# ASPLY.net
KiCad netlist of a schematic drawn in EAGLE
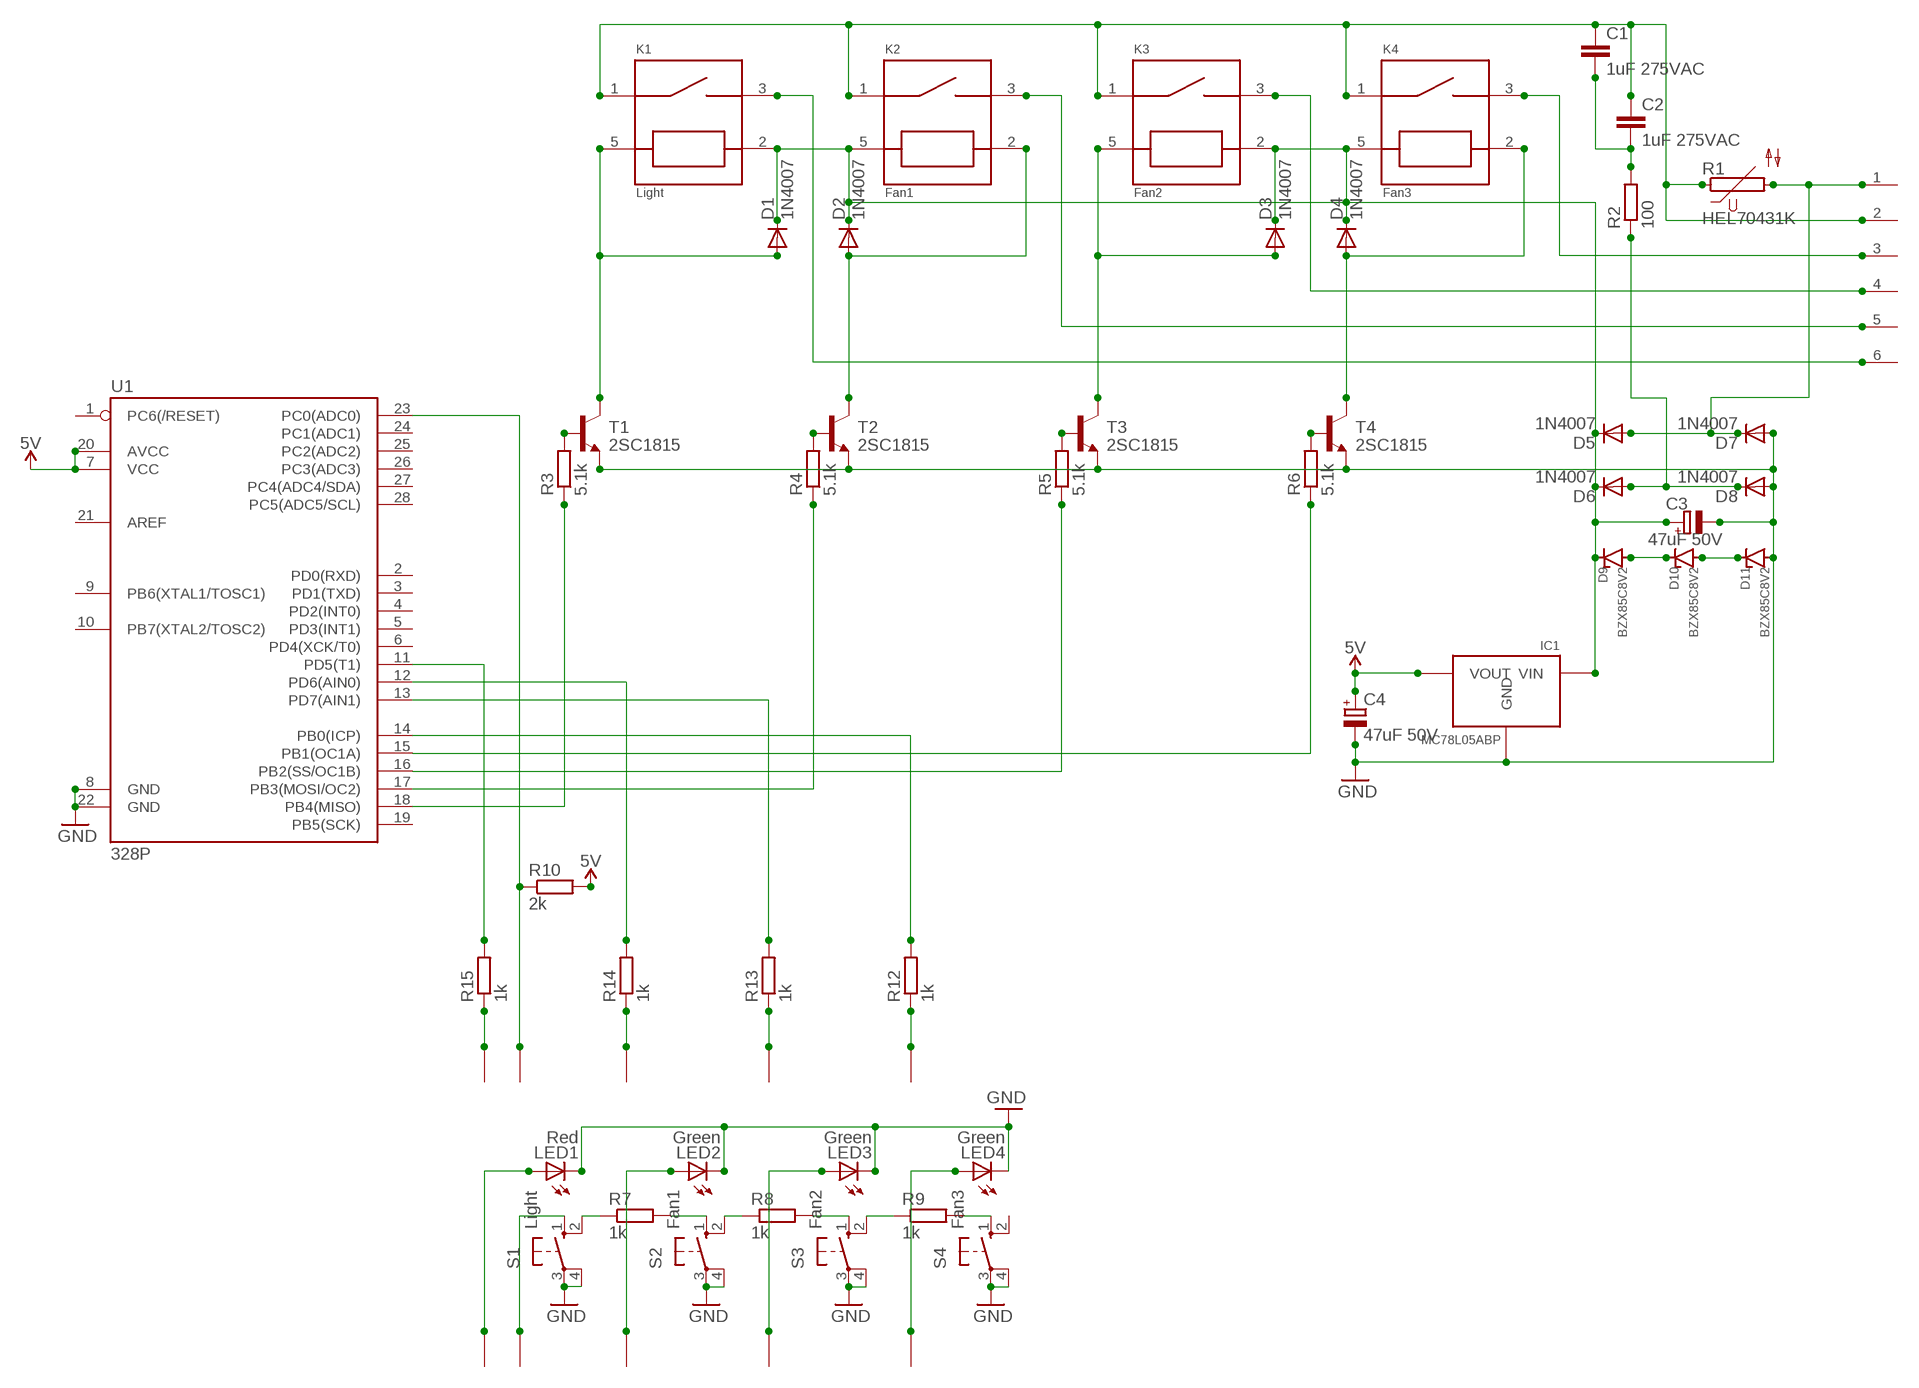
[diagram p0: schematic, sheet 1]

(export (version "E")
  (design (tool "Eeschema 10.0.6"))
  (components
    (comp (ref "C1")
      (value "1uF 275VAC")
      (footprint "eagle-import:C22.5B8")
      (libsource (lib "eagle-import") (part "C22/8"))
    )
    (comp (ref "C2")
      (value "1uF 275VAC")
      (footprint "eagle-import:C22.5B8")
      (libsource (lib "eagle-import") (part "C22/8"))
    )
    (comp (ref "C3")
      (value "47uF 50V")
      (footprint "eagle-import:E5-6")
      (libsource (lib "eagle-import") (part "CPOL-EUE5-6"))
    )
    (comp (ref "C4")
      (value "47uF 50V")
      (footprint "eagle-import:E5-6")
      (libsource (lib "eagle-import") (part "CPOL-EUE5-6"))
    )
    (comp (ref "D1")
      (value "1N4007")
      (footprint "eagle-import:DO41-10")
      (libsource (lib "eagle-import") (part "1N4004"))
    )
    (comp (ref "D2")
      (value "1N4007")
      (footprint "eagle-import:DO41-10")
      (libsource (lib "eagle-import") (part "1N4004"))
    )
    (comp (ref "D3")
      (value "1N4007")
      (footprint "eagle-import:DO41-10")
      (libsource (lib "eagle-import") (part "1N4004"))
    )
    (comp (ref "D4")
      (value "1N4007")
      (footprint "eagle-import:DO41-10")
      (libsource (lib "eagle-import") (part "1N4004"))
    )
    (comp (ref "D5")
      (value "1N4007")
      (footprint "eagle-import:DO41-10")
      (libsource (lib "eagle-import") (part "1N4004"))
    )
    (comp (ref "D6")
      (value "1N4007")
      (footprint "eagle-import:DO41-10")
      (libsource (lib "eagle-import") (part "1N4004"))
    )
    (comp (ref "D7")
      (value "1N4007")
      (footprint "eagle-import:DO41-10")
      (libsource (lib "eagle-import") (part "1N4004"))
    )
    (comp (ref "D8")
      (value "1N4007")
      (footprint "eagle-import:DO41-10")
      (libsource (lib "eagle-import") (part "1N4004"))
    )
    (comp (ref "D9")
      (value "BZX85C8V2")
      (footprint "eagle-import:STAB")
      (libsource (lib "eagle-import") (part "STAB"))
    )
    (comp (ref "D10")
      (value "BZX85C8V2")
      (footprint "eagle-import:STAB")
      (libsource (lib "eagle-import") (part "STAB"))
    )
    (comp (ref "D11")
      (value "BZX85C8V2")
      (footprint "eagle-import:STAB")
      (libsource (lib "eagle-import") (part "STAB"))
    )
    (comp (ref "IC1")
      (value "MC78L05ABP")
      (footprint "eagle-import:TO-92")
      (libsource (lib "eagle-import") (part "MC78L05ABP"))
    )
    (comp (ref "K1")
      (value "Light")
      (footprint "eagle-import:RELAY")
      (libsource (lib "eagle-import") (part "HJR-3FF-S-Z"))
    )
    (comp (ref "K2")
      (value "Fan1")
      (footprint "eagle-import:RELAY")
      (libsource (lib "eagle-import") (part "HJR-3FF-S-Z"))
    )
    (comp (ref "K3")
      (value "Fan2")
      (footprint "eagle-import:RELAY")
      (libsource (lib "eagle-import") (part "HJR-3FF-S-Z"))
    )
    (comp (ref "K4")
      (value "Fan3")
      (footprint "eagle-import:RELAY")
      (libsource (lib "eagle-import") (part "HJR-3FF-S-Z"))
    )
    (comp (ref "LED1")
      (value "Red")
      (footprint "eagle-import:LED3MM")
      (libsource (lib "eagle-import") (part "LED3MM"))
    )
    (comp (ref "LED2")
      (value "Green")
      (footprint "eagle-import:LED3MM")
      (libsource (lib "eagle-import") (part "LED3MM"))
    )
    (comp (ref "LED3")
      (value "Green")
      (footprint "eagle-import:LED3MM")
      (libsource (lib "eagle-import") (part "LED3MM"))
    )
    (comp (ref "LED4")
      (value "Green")
      (footprint "eagle-import:LED3MM")
      (libsource (lib "eagle-import") (part "LED3MM"))
    )
    (comp (ref "P1")
      (value "MOLEX")
      (footprint "eagle-import:MOLEX")
      (libsource (lib "eagle-import") (part "MOLEX"))
    )
    (comp (ref "R1")
      (value "HEL70431K")
      (footprint "eagle-import:S05K11")
      (libsource (lib "eagle-import") (part "S05K11"))
    )
    (comp (ref "R2")
      (value "100")
      (footprint "eagle-import:0617_22")
      (libsource (lib "eagle-import") (part "resistor_R-EU_0617/22"))
    )
    (comp (ref "R3")
      (value "5.1k")
      (footprint "eagle-import:0204_7")
      (libsource (lib "eagle-import") (part "R-EU_0204/7"))
    )
    (comp (ref "R4")
      (value "5.1k")
      (footprint "eagle-import:0204_7")
      (libsource (lib "eagle-import") (part "R-EU_0204/7"))
    )
    (comp (ref "R5")
      (value "5.1k")
      (footprint "eagle-import:0204_7")
      (libsource (lib "eagle-import") (part "R-EU_0204/7"))
    )
    (comp (ref "R6")
      (value "5.1k")
      (footprint "eagle-import:0204_7")
      (libsource (lib "eagle-import") (part "R-EU_0204/7"))
    )
    (comp (ref "R7")
      (value "1k")
      (footprint "eagle-import:0204_7")
      (libsource (lib "eagle-import") (part "R-EU_0204/7"))
    )
    (comp (ref "R8")
      (value "1k")
      (footprint "eagle-import:0204_7")
      (libsource (lib "eagle-import") (part "R-EU_0204/7"))
    )
    (comp (ref "R9")
      (value "1k")
      (footprint "eagle-import:0204_7")
      (libsource (lib "eagle-import") (part "R-EU_0204/7"))
    )
    (comp (ref "R10")
      (value "2k")
      (footprint "eagle-import:0204_7")
      (libsource (lib "eagle-import") (part "R-EU_0204/7"))
    )
    (comp (ref "R12")
      (value "1k")
      (footprint "eagle-import:0204_7")
      (libsource (lib "eagle-import") (part "R-EU_0204/7"))
    )
    (comp (ref "R13")
      (value "1k")
      (footprint "eagle-import:0204_7")
      (libsource (lib "eagle-import") (part "R-EU_0204/7"))
    )
    (comp (ref "R14")
      (value "1k")
      (footprint "eagle-import:0204_7")
      (libsource (lib "eagle-import") (part "R-EU_0204/7"))
    )
    (comp (ref "R15")
      (value "1k")
      (footprint "eagle-import:0204_7")
      (libsource (lib "eagle-import") (part "R-EU_0204/7"))
    )
    (comp (ref "S1")
      (value "Light")
      (footprint "eagle-import:B3F-10XX")
      (fields (field (name "MPN") "B3F-1000"))
      (libsource (lib "eagle-import") (part "10-XX"))
    )
    (comp (ref "S2")
      (value "Fan1")
      (footprint "eagle-import:B3F-10XX")
      (fields (field (name "MPN") "B3F-1000"))
      (libsource (lib "eagle-import") (part "10-XX"))
    )
    (comp (ref "S3")
      (value "Fan2")
      (footprint "eagle-import:B3F-10XX")
      (fields (field (name "MPN") "B3F-1000"))
      (libsource (lib "eagle-import") (part "10-XX"))
    )
    (comp (ref "S4")
      (value "Fan3")
      (footprint "eagle-import:B3F-10XX")
      (fields (field (name "MPN") "B3F-1000"))
      (libsource (lib "eagle-import") (part "10-XX"))
    )
    (comp (ref "T1")
      (value "2SC1815")
      (footprint "eagle-import:TO92-ECB")
      (libsource (lib "eagle-import") (part "2SC1815"))
    )
    (comp (ref "T2")
      (value "2SC1815")
      (footprint "eagle-import:TO92-ECB")
      (libsource (lib "eagle-import") (part "2SC1815"))
    )
    (comp (ref "T3")
      (value "2SC1815")
      (footprint "eagle-import:TO92-ECB")
      (libsource (lib "eagle-import") (part "2SC1815"))
    )
    (comp (ref "T4")
      (value "2SC1815")
      (footprint "eagle-import:TO92-ECB")
      (libsource (lib "eagle-import") (part "2SC1815"))
    )
    (comp (ref "U$1")
      (value "PIN")
      (footprint "eagle-import:PIN")
      (libsource (lib "eagle-import") (part "PIN"))
    )
    (comp (ref "U$3")
      (value "PIN")
      (footprint "eagle-import:PIN")
      (libsource (lib "eagle-import") (part "PIN"))
    )
    (comp (ref "U$5")
      (value "PIN")
      (footprint "eagle-import:PIN")
      (libsource (lib "eagle-import") (part "PIN"))
    )
    (comp (ref "U$7")
      (value "PIN")
      (footprint "eagle-import:PIN")
      (libsource (lib "eagle-import") (part "PIN"))
    )
    (comp (ref "U$8")
      (value "PIN")
      (footprint "eagle-import:PIN")
      (libsource (lib "eagle-import") (part "PIN"))
    )
    (comp (ref "U$13")
      (value "PIN")
      (footprint "eagle-import:PIN")
      (libsource (lib "eagle-import") (part "PIN"))
    )
    (comp (ref "U$14")
      (value "PIN")
      (footprint "eagle-import:PIN")
      (libsource (lib "eagle-import") (part "PIN"))
    )
    (comp (ref "U$16")
      (value "PIN")
      (footprint "eagle-import:PIN")
      (libsource (lib "eagle-import") (part "PIN"))
    )
    (comp (ref "U$18")
      (value "PIN")
      (footprint "eagle-import:PIN")
      (libsource (lib "eagle-import") (part "PIN"))
    )
    (comp (ref "U$20")
      (value "PIN")
      (footprint "eagle-import:PIN")
      (libsource (lib "eagle-import") (part "PIN"))
    )
    (comp (ref "U1")
      (value "328P")
      (footprint "eagle-import:DIP28")
      (libsource (lib "eagle-import") (part "ATMEGA328P_PDIP"))
    )
  )
  (nets
    (net (code "1") (name "5V") (class "Default")
      (node (ref "C4") (pin "+") (pinfunction "+_+") (pintype "passive"))
      (node (ref "IC1") (pin "P$1") (pinfunction "VOUT_P$1") (pintype "power_in"))
      (node (ref "R10") (pin "2") (pinfunction "2_2") (pintype "passive"))
      (node (ref "U1") (pin "20") (pinfunction "AVCC_20") (pintype "bidirectional"))
      (node (ref "U1") (pin "7") (pinfunction "VCC_7") (pintype "bidirectional"))
    )
    (net (code "2") (name "GND") (class "Default")
      (node (ref "C3") (pin "-") (pinfunction "-_-") (pintype "passive"))
      (node (ref "C4") (pin "-") (pinfunction "-_-") (pintype "passive"))
      (node (ref "D11") (pin "P$2") (pinfunction "P$2_P$2") (pintype "passive"))
      (node (ref "D7") (pin "A") (pinfunction "A_A") (pintype "passive"))
      (node (ref "D8") (pin "A") (pinfunction "A_A") (pintype "passive"))
      (node (ref "IC1") (pin "P$2") (pinfunction "GND_P$2") (pintype "power_in"))
      (node (ref "LED1") (pin "K") (pinfunction "C_K") (pintype "passive"))
      (node (ref "LED2") (pin "K") (pinfunction "C_K") (pintype "passive"))
      (node (ref "LED3") (pin "K") (pinfunction "C_K") (pintype "passive"))
      (node (ref "LED4") (pin "K") (pinfunction "C_K") (pintype "passive"))
      (node (ref "S1") (pin "3") (pinfunction "P_3") (pintype "passive"))
      (node (ref "S1") (pin "4") (pinfunction "P1_4") (pintype "passive"))
      (node (ref "S2") (pin "3") (pinfunction "P_3") (pintype "passive"))
      (node (ref "S2") (pin "4") (pinfunction "P1_4") (pintype "passive"))
      (node (ref "S3") (pin "3") (pinfunction "P_3") (pintype "passive"))
      (node (ref "S3") (pin "4") (pinfunction "P1_4") (pintype "passive"))
      (node (ref "S4") (pin "3") (pinfunction "P_3") (pintype "passive"))
      (node (ref "S4") (pin "4") (pinfunction "P1_4") (pintype "passive"))
      (node (ref "T1") (pin "E") (pinfunction "E_E") (pintype "passive"))
      (node (ref "T2") (pin "E") (pinfunction "E_E") (pintype "passive"))
      (node (ref "T3") (pin "E") (pinfunction "E_E") (pintype "passive"))
      (node (ref "T4") (pin "E") (pinfunction "E_E") (pintype "passive"))
      (node (ref "U1") (pin "22") (pinfunction "GND_22") (pintype "bidirectional"))
      (node (ref "U1") (pin "8") (pinfunction "GND_8") (pintype "bidirectional"))
    )
    (net (code "3") (name "Net-(C1-Pad2)") (class "Default")
      (node (ref "C1") (pin "2") (pinfunction "2_2") (pintype "passive"))
      (node (ref "C2") (pin "2") (pinfunction "2_2") (pintype "passive"))
      (node (ref "R2") (pin "2") (pinfunction "2_2") (pintype "passive"))
    )
    (net (code "4") (name "Net-(D6-PadA)") (class "Default")
      (node (ref "D6") (pin "A") (pinfunction "A_A") (pintype "passive"))
      (node (ref "D8") (pin "C") (pinfunction "C_C") (pintype "passive"))
      (node (ref "R2") (pin "1") (pinfunction "1_1") (pintype "passive"))
    )
    (net (code "5") (name "Net-(D10-PadP$1)") (class "Default")
      (node (ref "D10") (pin "P$1") (pinfunction "P$1_P$1") (pintype "passive"))
      (node (ref "D9") (pin "P$2") (pinfunction "P$2_P$2") (pintype "passive"))
    )
    (net (code "6") (name "Net-(D10-PadP$2)") (class "Default")
      (node (ref "D10") (pin "P$2") (pinfunction "P$2_P$2") (pintype "passive"))
      (node (ref "D11") (pin "P$1") (pinfunction "P$1_P$1") (pintype "passive"))
    )
    (net (code "7") (name "Net-(IC1-VIN)") (class "Default")
      (node (ref "C3") (pin "+") (pinfunction "+_+") (pintype "passive"))
      (node (ref "D1") (pin "C") (pinfunction "C_C") (pintype "passive"))
      (node (ref "D2") (pin "C") (pinfunction "C_C") (pintype "passive"))
      (node (ref "D3") (pin "C") (pinfunction "C_C") (pintype "passive"))
      (node (ref "D4") (pin "C") (pinfunction "C_C") (pintype "passive"))
      (node (ref "D5") (pin "C") (pinfunction "C_C") (pintype "passive"))
      (node (ref "D6") (pin "C") (pinfunction "C_C") (pintype "passive"))
      (node (ref "D9") (pin "P$1") (pinfunction "P$1_P$1") (pintype "passive"))
      (node (ref "IC1") (pin "P$3") (pinfunction "VIN_P$3") (pintype "power_in"))
      (node (ref "K1") (pin "2") (pinfunction "P$2_2") (pintype "passive"))
      (node (ref "K2") (pin "5") (pinfunction "P$5_5") (pintype "passive"))
      (node (ref "K3") (pin "2") (pinfunction "P$2_2") (pintype "passive"))
      (node (ref "K4") (pin "5") (pinfunction "P$5_5") (pintype "passive"))
    )
    (net (code "8") (name "Net-(K1-P$1)") (class "Default")
      (node (ref "C1") (pin "1") (pinfunction "1_1") (pintype "passive"))
      (node (ref "C2") (pin "1") (pinfunction "1_1") (pintype "passive"))
      (node (ref "K1") (pin "1") (pinfunction "P$1_1") (pintype "passive"))
      (node (ref "K2") (pin "1") (pinfunction "P$1_1") (pintype "passive"))
      (node (ref "K3") (pin "1") (pinfunction "P$1_1") (pintype "passive"))
      (node (ref "K4") (pin "1") (pinfunction "P$1_1") (pintype "passive"))
      (node (ref "P1") (pin "2") (pinfunction "P$2_2") (pintype "passive"))
      (node (ref "R1") (pin "1") (pinfunction "1_1") (pintype "passive"))
    )
    (net (code "9") (name "Net-(K1-P$3)") (class "Default")
      (node (ref "K1") (pin "3") (pinfunction "P$3_3") (pintype "passive"))
      (node (ref "P1") (pin "6") (pinfunction "P$6_6") (pintype "passive"))
    )
    (net (code "10") (name "Net-(K1-P$5)") (class "Default")
      (node (ref "D1") (pin "A") (pinfunction "A_A") (pintype "passive"))
      (node (ref "K1") (pin "5") (pinfunction "P$5_5") (pintype "passive"))
      (node (ref "T1") (pin "C") (pinfunction "C_C") (pintype "passive"))
    )
    (net (code "11") (name "Net-(K2-P$2)") (class "Default")
      (node (ref "D2") (pin "A") (pinfunction "A_A") (pintype "passive"))
      (node (ref "K2") (pin "2") (pinfunction "P$2_2") (pintype "passive"))
      (node (ref "T2") (pin "C") (pinfunction "C_C") (pintype "passive"))
    )
    (net (code "12") (name "Net-(K2-P$3)") (class "Default")
      (node (ref "K2") (pin "3") (pinfunction "P$3_3") (pintype "passive"))
      (node (ref "P1") (pin "5") (pinfunction "P$5_5") (pintype "passive"))
    )
    (net (code "13") (name "Net-(K3-P$3)") (class "Default")
      (node (ref "K3") (pin "3") (pinfunction "P$3_3") (pintype "passive"))
      (node (ref "P1") (pin "4") (pinfunction "P$4_4") (pintype "passive"))
    )
    (net (code "14") (name "Net-(K3-P$5)") (class "Default")
      (node (ref "D3") (pin "A") (pinfunction "A_A") (pintype "passive"))
      (node (ref "K3") (pin "5") (pinfunction "P$5_5") (pintype "passive"))
      (node (ref "T3") (pin "C") (pinfunction "C_C") (pintype "passive"))
    )
    (net (code "15") (name "Net-(K4-P$2)") (class "Default")
      (node (ref "D4") (pin "A") (pinfunction "A_A") (pintype "passive"))
      (node (ref "K4") (pin "2") (pinfunction "P$2_2") (pintype "passive"))
      (node (ref "T4") (pin "C") (pinfunction "C_C") (pintype "passive"))
    )
    (net (code "16") (name "Net-(K4-P$3)") (class "Default")
      (node (ref "K4") (pin "3") (pinfunction "P$3_3") (pintype "passive"))
      (node (ref "P1") (pin "3") (pinfunction "P$3_3") (pintype "passive"))
    )
    (net (code "17") (name "Net-(P1-P$1)") (class "Default")
      (node (ref "D5") (pin "A") (pinfunction "A_A") (pintype "passive"))
      (node (ref "D7") (pin "C") (pinfunction "C_C") (pintype "passive"))
      (node (ref "P1") (pin "1") (pinfunction "P$1_1") (pintype "passive"))
      (node (ref "R1") (pin "2") (pinfunction "2_2") (pintype "passive"))
    )
    (net (code "18") (name "Net-(R3-Pad2)") (class "Default")
      (node (ref "R3") (pin "2") (pinfunction "2_2") (pintype "passive"))
      (node (ref "T1") (pin "B") (pinfunction "B_B") (pintype "passive"))
    )
    (net (code "19") (name "Net-(R4-Pad2)") (class "Default")
      (node (ref "R4") (pin "2") (pinfunction "2_2") (pintype "passive"))
      (node (ref "T2") (pin "B") (pinfunction "B_B") (pintype "passive"))
    )
    (net (code "20") (name "Net-(R5-Pad2)") (class "Default")
      (node (ref "R5") (pin "2") (pinfunction "2_2") (pintype "passive"))
      (node (ref "T3") (pin "B") (pinfunction "B_B") (pintype "passive"))
    )
    (net (code "21") (name "Net-(R6-Pad2)") (class "Default")
      (node (ref "R6") (pin "2") (pinfunction "2_2") (pintype "passive"))
      (node (ref "T4") (pin "B") (pinfunction "B_B") (pintype "passive"))
    )
    (net (code "22") (name "Net-(S1-S)") (class "Default")
      (node (ref "S1") (pin "1") (pinfunction "S_1") (pintype "passive"))
      (node (ref "U$13") (pin "P$1") (pinfunction "1_P$1") (pintype "passive"))
    )
    (net (code "23") (name "Net-(S1-S1)") (class "Default")
      (node (ref "R7") (pin "1") (pinfunction "1_1") (pintype "passive"))
      (node (ref "S1") (pin "2") (pinfunction "S1_2") (pintype "passive"))
    )
    (net (code "24") (name "Net-(S2-S)") (class "Default")
      (node (ref "R7") (pin "2") (pinfunction "2_2") (pintype "passive"))
      (node (ref "S2") (pin "1") (pinfunction "S_1") (pintype "passive"))
    )
    (net (code "25") (name "Net-(S2-S1)") (class "Default")
      (node (ref "R8") (pin "1") (pinfunction "1_1") (pintype "passive"))
      (node (ref "S2") (pin "2") (pinfunction "S1_2") (pintype "passive"))
    )
    (net (code "26") (name "Net-(S3-S)") (class "Default")
      (node (ref "R8") (pin "2") (pinfunction "2_2") (pintype "passive"))
      (node (ref "S3") (pin "1") (pinfunction "S_1") (pintype "passive"))
    )
    (net (code "27") (name "Net-(S3-S1)") (class "Default")
      (node (ref "R9") (pin "1") (pinfunction "1_1") (pintype "passive"))
      (node (ref "S3") (pin "2") (pinfunction "S1_2") (pintype "passive"))
    )
    (net (code "28") (name "Net-(S4-S)") (class "Default")
      (node (ref "R9") (pin "2") (pinfunction "2_2") (pintype "passive"))
      (node (ref "S4") (pin "1") (pinfunction "S_1") (pintype "passive"))
    )
    (net (code "29") (name "Net-(U$1-1)") (class "Default")
      (node (ref "R15") (pin "1") (pinfunction "1_1") (pintype "passive"))
      (node (ref "U$1") (pin "P$1") (pinfunction "1_P$1") (pintype "passive"))
    )
    (net (code "30") (name "Net-(U$3-1)") (class "Default")
      (node (ref "R14") (pin "1") (pinfunction "1_1") (pintype "passive"))
      (node (ref "U$3") (pin "P$1") (pinfunction "1_P$1") (pintype "passive"))
    )
    (net (code "31") (name "Net-(U$5-1)") (class "Default")
      (node (ref "R13") (pin "1") (pinfunction "1_1") (pintype "passive"))
      (node (ref "U$5") (pin "P$1") (pinfunction "1_P$1") (pintype "passive"))
    )
    (net (code "32") (name "Net-(U$7-1)") (class "Default")
      (node (ref "R12") (pin "1") (pinfunction "1_1") (pintype "passive"))
      (node (ref "U$7") (pin "P$1") (pinfunction "1_P$1") (pintype "passive"))
    )
    (net (code "33") (name "Net-(U$8-1)") (class "Default")
      (node (ref "R10") (pin "1") (pinfunction "1_1") (pintype "passive"))
      (node (ref "U$8") (pin "P$1") (pinfunction "1_P$1") (pintype "passive"))
      (node (ref "U1") (pin "23") (pinfunction "PC0(ADC0)_23") (pintype "bidirectional"))
    )
    (net (code "34") (name "Net-(U$14-1)") (class "Default")
      (node (ref "LED4") (pin "A") (pinfunction "A_A") (pintype "passive"))
      (node (ref "U$14") (pin "P$1") (pinfunction "1_P$1") (pintype "passive"))
    )
    (net (code "35") (name "Net-(U$16-1)") (class "Default")
      (node (ref "LED3") (pin "A") (pinfunction "A_A") (pintype "passive"))
      (node (ref "U$16") (pin "P$1") (pinfunction "1_P$1") (pintype "passive"))
    )
    (net (code "36") (name "Net-(U$18-1)") (class "Default")
      (node (ref "LED2") (pin "A") (pinfunction "A_A") (pintype "passive"))
      (node (ref "U$18") (pin "P$1") (pinfunction "1_P$1") (pintype "passive"))
    )
    (net (code "37") (name "Net-(U$20-1)") (class "Default")
      (node (ref "LED1") (pin "A") (pinfunction "A_A") (pintype "passive"))
      (node (ref "U$20") (pin "P$1") (pinfunction "1_P$1") (pintype "passive"))
    )
    (net (code "38") (name "Net-(U1-PB0(ICP))") (class "Default")
      (node (ref "R12") (pin "2") (pinfunction "2_2") (pintype "passive"))
      (node (ref "U1") (pin "14") (pinfunction "PB0(ICP)_14") (pintype "bidirectional"))
    )
    (net (code "39") (name "Net-(U1-PB1(OC1A))") (class "Default")
      (node (ref "R6") (pin "1") (pinfunction "1_1") (pintype "passive"))
      (node (ref "U1") (pin "15") (pinfunction "PB1(OC1A)_15") (pintype "bidirectional"))
    )
    (net (code "40") (name "Net-(U1-PB2(SS{slash}OC1B))") (class "Default")
      (node (ref "R5") (pin "1") (pinfunction "1_1") (pintype "passive"))
      (node (ref "U1") (pin "16") (pinfunction "PB2(SS/OC1B)_16") (pintype "bidirectional"))
    )
    (net (code "41") (name "Net-(U1-PB3(MOSI{slash}OC2))") (class "Default")
      (node (ref "R4") (pin "1") (pinfunction "1_1") (pintype "passive"))
      (node (ref "U1") (pin "17") (pinfunction "PB3(MOSI/OC2)_17") (pintype "bidirectional"))
    )
    (net (code "42") (name "Net-(U1-PB4(MISO))") (class "Default")
      (node (ref "R3") (pin "1") (pinfunction "1_1") (pintype "passive"))
      (node (ref "U1") (pin "18") (pinfunction "PB4(MISO)_18") (pintype "bidirectional"))
    )
    (net (code "43") (name "Net-(U1-PD5(T1))") (class "Default")
      (node (ref "R15") (pin "2") (pinfunction "2_2") (pintype "passive"))
      (node (ref "U1") (pin "11") (pinfunction "PD5(T1)_11") (pintype "bidirectional"))
    )
    (net (code "44") (name "Net-(U1-PD6(AIN0))") (class "Default")
      (node (ref "R14") (pin "2") (pinfunction "2_2") (pintype "passive"))
      (node (ref "U1") (pin "12") (pinfunction "PD6(AIN0)_12") (pintype "bidirectional"))
    )
    (net (code "45") (name "Net-(U1-PD7(AIN1))") (class "Default")
      (node (ref "R13") (pin "2") (pinfunction "2_2") (pintype "passive"))
      (node (ref "U1") (pin "13") (pinfunction "PD7(AIN1)_13") (pintype "bidirectional"))
    )
    (net (code "46") (name "unconnected-(S4-S1-Pad2)") (class "Default")
      (node (ref "S4") (pin "2") (pinfunction "S1_2") (pintype "passive"))
    )
    (net (code "47") (name "unconnected-(U1-AREF-Pad21)") (class "Default")
      (node (ref "U1") (pin "21") (pinfunction "AREF_21") (pintype "bidirectional"))
    )
    (net (code "48") (name "unconnected-(U1-PB5(SCK)-Pad19)") (class "Default")
      (node (ref "U1") (pin "19") (pinfunction "PB5(SCK)_19") (pintype "bidirectional"))
    )
    (net (code "49") (name "unconnected-(U1-PB6(XTAL1{slash}TOSC1)-Pad9)") (class "Default")
      (node (ref "U1") (pin "9") (pinfunction "PB6(XTAL1/TOSC1)_9") (pintype "bidirectional"))
    )
    (net (code "50") (name "unconnected-(U1-PB7(XTAL2{slash}TOSC2)-Pad10)") (class "Default")
      (node (ref "U1") (pin "10") (pinfunction "PB7(XTAL2/TOSC2)_10") (pintype "bidirectional"))
    )
    (net (code "51") (name "unconnected-(U1-PC1(ADC1)-Pad24)") (class "Default")
      (node (ref "U1") (pin "24") (pinfunction "PC1(ADC1)_24") (pintype "bidirectional"))
    )
    (net (code "52") (name "unconnected-(U1-PC2(ADC2)-Pad25)") (class "Default")
      (node (ref "U1") (pin "25") (pinfunction "PC2(ADC2)_25") (pintype "bidirectional"))
    )
    (net (code "53") (name "unconnected-(U1-PC3(ADC3)-Pad26)") (class "Default")
      (node (ref "U1") (pin "26") (pinfunction "PC3(ADC3)_26") (pintype "bidirectional"))
    )
    (net (code "54") (name "unconnected-(U1-PC4(ADC4{slash}SDA)-Pad27)") (class "Default")
      (node (ref "U1") (pin "27") (pinfunction "PC4(ADC4/SDA)_27") (pintype "bidirectional"))
    )
    (net (code "55") (name "unconnected-(U1-PC5(ADC5{slash}SCL)-Pad28)") (class "Default")
      (node (ref "U1") (pin "28") (pinfunction "PC5(ADC5/SCL)_28") (pintype "bidirectional"))
    )
    (net (code "56") (name "unconnected-(U1-PC6({slash}RESET)-Pad1)") (class "Default")
      (node (ref "U1") (pin "1") (pinfunction "PC6(/RESET)_1") (pintype "bidirectional"))
    )
    (net (code "57") (name "unconnected-(U1-PD0(RXD)-Pad2)") (class "Default")
      (node (ref "U1") (pin "2") (pinfunction "PD0(RXD)_2") (pintype "bidirectional"))
    )
    (net (code "58") (name "unconnected-(U1-PD1(TXD)-Pad3)") (class "Default")
      (node (ref "U1") (pin "3") (pinfunction "PD1(TXD)_3") (pintype "bidirectional"))
    )
    (net (code "59") (name "unconnected-(U1-PD2(INT0)-Pad4)") (class "Default")
      (node (ref "U1") (pin "4") (pinfunction "PD2(INT0)_4") (pintype "bidirectional"))
    )
    (net (code "60") (name "unconnected-(U1-PD3(INT1)-Pad5)") (class "Default")
      (node (ref "U1") (pin "5") (pinfunction "PD3(INT1)_5") (pintype "bidirectional"))
    )
    (net (code "61") (name "unconnected-(U1-PD4(XCK{slash}T0)-Pad6)") (class "Default")
      (node (ref "U1") (pin "6") (pinfunction "PD4(XCK/T0)_6") (pintype "bidirectional"))
    )
  )
)
